# dv_mcu_mem.net
KiCad netlist of a schematic drawn in Altium Designer
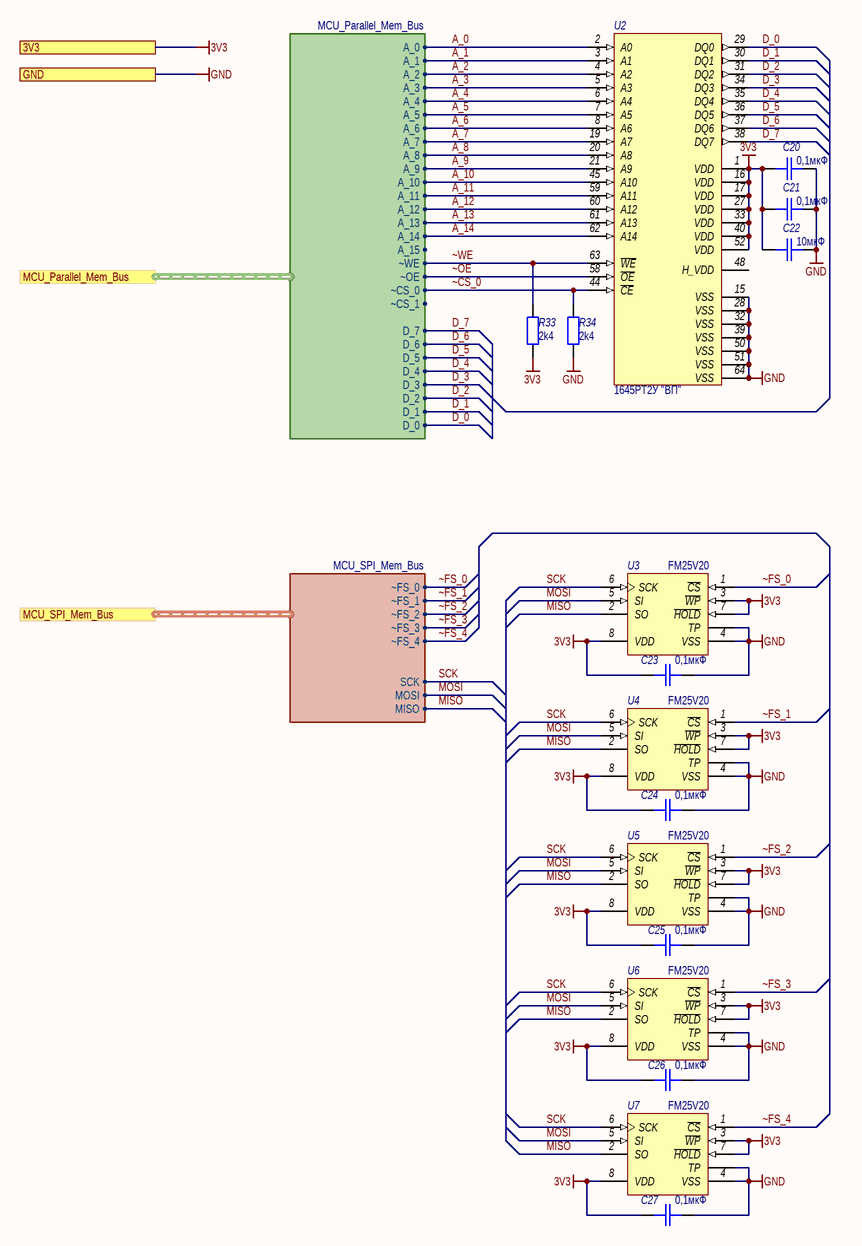
[diagram p0: dv_mcu_mem.SchDoc]

(export (version "E")
  (design (tool "Eeschema 10.0.6"))
  (components
    (comp (ref "C20")
      (value "0,1мкФ")
      (footprint "SMD_C0805")
      (description "Capacitor")
      (fields (field (name "Comment") "K10-79"))
      (libsource (lib "Passive") (part "Capacitor"))
    )
    (comp (ref "C21")
      (value "0,1мкФ")
      (footprint "SMD_C0805")
      (description "Capacitor")
      (fields (field (name "Comment") "K10-79"))
      (libsource (lib "Passive") (part "Capacitor"))
    )
    (comp (ref "C22")
      (value "10мкФ")
      (footprint "SMD_C0805")
      (description "Capacitor")
      (fields (field (name "Comment") "K10-79"))
      (libsource (lib "Passive") (part "Capacitor"))
    )
    (comp (ref "C23")
      (value "0,1мкФ")
      (footprint "SMD_C0805")
      (description "Capacitor")
      (fields (field (name "Comment") "K10-79"))
      (libsource (lib "Passive") (part "Capacitor"))
    )
    (comp (ref "C24")
      (value "0,1мкФ")
      (footprint "SMD_C0805")
      (description "Capacitor")
      (fields (field (name "Comment") "K10-79"))
      (libsource (lib "Passive") (part "Capacitor"))
    )
    (comp (ref "C25")
      (value "0,1мкФ")
      (footprint "SMD_C0805")
      (description "Capacitor")
      (fields (field (name "Comment") "K10-79"))
      (libsource (lib "Passive") (part "Capacitor"))
    )
    (comp (ref "C26")
      (value "0,1мкФ")
      (footprint "SMD_C0805")
      (description "Capacitor")
      (fields (field (name "Comment") "K10-79"))
      (libsource (lib "Passive") (part "Capacitor"))
    )
    (comp (ref "C27")
      (value "0,1мкФ")
      (footprint "SMD_C0805")
      (description "Capacitor")
      (fields (field (name "Comment") "K10-79"))
      (libsource (lib "Passive") (part "Capacitor"))
    )
    (comp (ref "R33")
      (value "2k4")
      (footprint "SMD_0805")
      (description "Resistor")
      (fields (field (name "Comment") "OSM R1-12"))
      (libsource (lib "Passive") (part "Resistor"))
    )
    (comp (ref "R34")
      (value "2k4")
      (footprint "SMD_0805")
      (description "Resistor")
      (fields (field (name "Comment") "OSM R1-12"))
      (libsource (lib "Passive") (part "Resistor"))
    )
    (comp (ref "U2")
      (value "1645RT2U VP")
      (footprint "5134.64-6")
      (fields (field (name "НАИМЕНОВАНИЕ") "1645РТ2У \"ВП\""))
      (libsource (lib "1645RT2U") (part "1645RT2U"))
    )
    (comp (ref "U3")
      (value "FM25V20")
      (footprint "TDFN-8_6x5")
      (description "2Mb Serial 3V FRAM Memory")
      (fields (field (name "НАИМЕНОВАНИЕ") "FM25V20"))
      (libsource (lib "Memory") (part "FM25V"))
    )
    (comp (ref "U4")
      (value "FM25V20")
      (footprint "TDFN-8_6x5")
      (description "2Mb Serial 3V FRAM Memory")
      (fields (field (name "НАИМЕНОВАНИЕ") "FM25V20"))
      (libsource (lib "Memory") (part "FM25V"))
    )
    (comp (ref "U5")
      (value "FM25V20")
      (footprint "TDFN-8_6x5")
      (description "2Mb Serial 3V FRAM Memory")
      (fields (field (name "НАИМЕНОВАНИЕ") "FM25V20"))
      (libsource (lib "Memory") (part "FM25V"))
    )
    (comp (ref "U6")
      (value "FM25V20")
      (footprint "TDFN-8_6x5")
      (description "2Mb Serial 3V FRAM Memory")
      (fields (field (name "НАИМЕНОВАНИЕ") "FM25V20"))
      (libsource (lib "Memory") (part "FM25V"))
    )
    (comp (ref "U7")
      (value "FM25V20")
      (footprint "TDFN-8_6x5")
      (description "2Mb Serial 3V FRAM Memory")
      (fields (field (name "НАИМЕНОВАНИЕ") "FM25V20"))
      (libsource (lib "Memory") (part "FM25V"))
    )
  )
  (nets
    (net (code "3") (name "/A_0") (class "Default")
      (node (ref "U2") (pin "2") (pinfunction "A0_2") (pintype "input"))
    )
    (net (code "4") (name "/A_1") (class "Default")
      (node (ref "U2") (pin "3") (pinfunction "A1_3") (pintype "input"))
    )
    (net (code "5") (name "/A_2") (class "Default")
      (node (ref "U2") (pin "4") (pinfunction "A2_4") (pintype "input"))
    )
    (net (code "6") (name "/A_3") (class "Default")
      (node (ref "U2") (pin "5") (pinfunction "A3_5") (pintype "input"))
    )
    (net (code "7") (name "/A_4") (class "Default")
      (node (ref "U2") (pin "6") (pinfunction "A4_6") (pintype "input"))
    )
    (net (code "8") (name "/A_5") (class "Default")
      (node (ref "U2") (pin "7") (pinfunction "A5_7") (pintype "input"))
    )
    (net (code "9") (name "/A_6") (class "Default")
      (node (ref "U2") (pin "8") (pinfunction "A6_8") (pintype "input"))
    )
    (net (code "10") (name "/A_7") (class "Default")
      (node (ref "U2") (pin "19") (pinfunction "A7_19") (pintype "input"))
    )
    (net (code "11") (name "/A_8") (class "Default")
      (node (ref "U2") (pin "20") (pinfunction "A8_20") (pintype "input"))
    )
    (net (code "12") (name "/A_9") (class "Default")
      (node (ref "U2") (pin "21") (pinfunction "A9_21") (pintype "input"))
    )
    (net (code "13") (name "/A_10") (class "Default")
      (node (ref "U2") (pin "45") (pinfunction "A10_45") (pintype "input"))
    )
    (net (code "14") (name "/A_11") (class "Default")
      (node (ref "U2") (pin "59") (pinfunction "A11_59") (pintype "input"))
    )
    (net (code "15") (name "/A_12") (class "Default")
      (node (ref "U2") (pin "60") (pinfunction "A12_60") (pintype "input"))
    )
    (net (code "16") (name "/A_13") (class "Default")
      (node (ref "U2") (pin "61") (pinfunction "A13_61") (pintype "input"))
    )
    (net (code "17") (name "/A_14") (class "Default")
      (node (ref "U2") (pin "62") (pinfunction "A14_62") (pintype "input"))
    )
    (net (code "18") (name "/D_0") (class "Default")
      (node (ref "U2") (pin "29") (pinfunction "DQ0_29") (pintype "output"))
    )
    (net (code "19") (name "/D_1") (class "Default")
      (node (ref "U2") (pin "30") (pinfunction "DQ1_30") (pintype "output"))
    )
    (net (code "20") (name "/D_2") (class "Default")
      (node (ref "U2") (pin "31") (pinfunction "DQ2_31") (pintype "output"))
    )
    (net (code "21") (name "/D_3") (class "Default")
      (node (ref "U2") (pin "34") (pinfunction "DQ3_34") (pintype "output"))
    )
    (net (code "22") (name "/D_4") (class "Default")
      (node (ref "U2") (pin "35") (pinfunction "DQ4_35") (pintype "output"))
    )
    (net (code "23") (name "/D_5") (class "Default")
      (node (ref "U2") (pin "36") (pinfunction "DQ5_36") (pintype "output"))
    )
    (net (code "24") (name "/D_6") (class "Default")
      (node (ref "U2") (pin "37") (pinfunction "DQ6_37") (pintype "output"))
    )
    (net (code "25") (name "/D_7") (class "Default")
      (node (ref "U2") (pin "38") (pinfunction "DQ7_38") (pintype "output"))
    )
    (net (code "26") (name "/MISO") (class "Default")
      (node (ref "U3") (pin "2") (pinfunction "SO_2") (pintype "tri_state"))
      (node (ref "U4") (pin "2") (pinfunction "SO_2") (pintype "tri_state"))
      (node (ref "U5") (pin "2") (pinfunction "SO_2") (pintype "tri_state"))
      (node (ref "U6") (pin "2") (pinfunction "SO_2") (pintype "tri_state"))
      (node (ref "U7") (pin "2") (pinfunction "SO_2") (pintype "tri_state"))
    )
    (net (code "27") (name "/MOSI") (class "Default")
      (node (ref "U3") (pin "5") (pinfunction "SI_5") (pintype "input"))
      (node (ref "U4") (pin "5") (pinfunction "SI_5") (pintype "input"))
      (node (ref "U5") (pin "5") (pinfunction "SI_5") (pintype "input"))
      (node (ref "U6") (pin "5") (pinfunction "SI_5") (pintype "input"))
      (node (ref "U7") (pin "5") (pinfunction "SI_5") (pintype "input"))
    )
    (net (code "28") (name "/SCK") (class "Default")
      (node (ref "U3") (pin "6") (pinfunction "SCK_6") (pintype "input"))
      (node (ref "U4") (pin "6") (pinfunction "SCK_6") (pintype "input"))
      (node (ref "U5") (pin "6") (pinfunction "SCK_6") (pintype "input"))
      (node (ref "U6") (pin "6") (pinfunction "SCK_6") (pintype "input"))
      (node (ref "U7") (pin "6") (pinfunction "SCK_6") (pintype "input"))
    )
    (net (code "31") (name "/~CS_0") (class "Default")
      (node (ref "R34") (pin "2") (pinfunction "2_2") (pintype "passive"))
      (node (ref "U2") (pin "44") (pinfunction "~{CE}_44") (pintype "input"))
    )
    (net (code "32") (name "/~FS_0") (class "Default")
      (node (ref "U3") (pin "1") (pinfunction "~{CS}_1") (pintype "input"))
    )
    (net (code "33") (name "/~FS_1") (class "Default")
      (node (ref "U4") (pin "1") (pinfunction "~{CS}_1") (pintype "input"))
    )
    (net (code "34") (name "/~FS_2") (class "Default")
      (node (ref "U5") (pin "1") (pinfunction "~{CS}_1") (pintype "input"))
    )
    (net (code "35") (name "/~FS_3") (class "Default")
      (node (ref "U6") (pin "1") (pinfunction "~{CS}_1") (pintype "input"))
    )
    (net (code "36") (name "/~FS_4") (class "Default")
      (node (ref "U7") (pin "1") (pinfunction "~{CS}_1") (pintype "input"))
    )
    (net (code "37") (name "/~OE") (class "Default")
      (node (ref "U2") (pin "58") (pinfunction "~{OE}_58") (pintype "input"))
    )
    (net (code "38") (name "/~WE") (class "Default")
      (node (ref "R33") (pin "2") (pinfunction "2_2") (pintype "passive"))
      (node (ref "U2") (pin "63") (pinfunction "~{WE}_63") (pintype "input"))
    )
    (net (code "39") (name "3V3") (class "Default")
      (node (ref "C20") (pin "1") (pinfunction "1_1") (pintype "passive"))
      (node (ref "C21") (pin "1") (pinfunction "1_1") (pintype "passive"))
      (node (ref "C22") (pin "2") (pinfunction "2_2") (pintype "passive"))
      (node (ref "C23") (pin "2") (pinfunction "2_2") (pintype "passive"))
      (node (ref "C24") (pin "2") (pinfunction "2_2") (pintype "passive"))
      (node (ref "C25") (pin "2") (pinfunction "2_2") (pintype "passive"))
      (node (ref "C26") (pin "2") (pinfunction "2_2") (pintype "passive"))
      (node (ref "C27") (pin "2") (pinfunction "2_2") (pintype "passive"))
      (node (ref "R33") (pin "1") (pinfunction "1_1") (pintype "passive"))
      (node (ref "U2") (pin "1") (pinfunction "VDD_1") (pintype "power_in"))
      (node (ref "U2") (pin "16") (pinfunction "VDD_16") (pintype "power_in"))
      (node (ref "U2") (pin "17") (pinfunction "VDD_17") (pintype "power_in"))
      (node (ref "U2") (pin "27") (pinfunction "VDD_27") (pintype "power_in"))
      (node (ref "U2") (pin "33") (pinfunction "VDD_33") (pintype "power_in"))
      (node (ref "U2") (pin "40") (pinfunction "VDD_40") (pintype "power_in"))
      (node (ref "U2") (pin "52") (pinfunction "VDD_52") (pintype "power_in"))
      (node (ref "U3") (pin "3") (pinfunction "~{WP}_3") (pintype "input"))
      (node (ref "U3") (pin "7") (pinfunction "~{HOLD}_7") (pintype "input"))
      (node (ref "U3") (pin "8") (pinfunction "VDD_8") (pintype "power_in"))
      (node (ref "U4") (pin "3") (pinfunction "~{WP}_3") (pintype "input"))
      (node (ref "U4") (pin "7") (pinfunction "~{HOLD}_7") (pintype "input"))
      (node (ref "U4") (pin "8") (pinfunction "VDD_8") (pintype "power_in"))
      (node (ref "U5") (pin "3") (pinfunction "~{WP}_3") (pintype "input"))
      (node (ref "U5") (pin "7") (pinfunction "~{HOLD}_7") (pintype "input"))
      (node (ref "U5") (pin "8") (pinfunction "VDD_8") (pintype "power_in"))
      (node (ref "U6") (pin "3") (pinfunction "~{WP}_3") (pintype "input"))
      (node (ref "U6") (pin "7") (pinfunction "~{HOLD}_7") (pintype "input"))
      (node (ref "U6") (pin "8") (pinfunction "VDD_8") (pintype "power_in"))
      (node (ref "U7") (pin "3") (pinfunction "~{WP}_3") (pintype "input"))
      (node (ref "U7") (pin "7") (pinfunction "~{HOLD}_7") (pintype "input"))
      (node (ref "U7") (pin "8") (pinfunction "VDD_8") (pintype "power_in"))
    )
    (net (code "40") (name "GND") (class "Default")
      (node (ref "C20") (pin "2") (pinfunction "2_2") (pintype "passive"))
      (node (ref "C21") (pin "2") (pinfunction "2_2") (pintype "passive"))
      (node (ref "C22") (pin "1") (pinfunction "1_1") (pintype "passive"))
      (node (ref "C23") (pin "1") (pinfunction "1_1") (pintype "passive"))
      (node (ref "C24") (pin "1") (pinfunction "1_1") (pintype "passive"))
      (node (ref "C25") (pin "1") (pinfunction "1_1") (pintype "passive"))
      (node (ref "C26") (pin "1") (pinfunction "1_1") (pintype "passive"))
      (node (ref "C27") (pin "1") (pinfunction "1_1") (pintype "passive"))
      (node (ref "R34") (pin "1") (pinfunction "1_1") (pintype "passive"))
      (node (ref "U2") (pin "15") (pinfunction "VSS_15") (pintype "power_in"))
      (node (ref "U2") (pin "28") (pinfunction "VSS_28") (pintype "power_in"))
      (node (ref "U2") (pin "32") (pinfunction "VSS_32") (pintype "power_in"))
      (node (ref "U2") (pin "39") (pinfunction "VSS_39") (pintype "power_in"))
      (node (ref "U2") (pin "50") (pinfunction "VSS_50") (pintype "power_in"))
      (node (ref "U2") (pin "51") (pinfunction "VSS_51") (pintype "power_in"))
      (node (ref "U2") (pin "64") (pinfunction "VSS_64") (pintype "power_in"))
      (node (ref "U3") (pin "4") (pinfunction "VSS_4") (pintype "power_in"))
      (node (ref "U3") (pin "TP") (pinfunction "TP_TP") (pintype "power_in"))
      (node (ref "U4") (pin "4") (pinfunction "VSS_4") (pintype "power_in"))
      (node (ref "U4") (pin "TP") (pinfunction "TP_TP") (pintype "power_in"))
      (node (ref "U5") (pin "4") (pinfunction "VSS_4") (pintype "power_in"))
      (node (ref "U5") (pin "TP") (pinfunction "TP_TP") (pintype "power_in"))
      (node (ref "U6") (pin "4") (pinfunction "VSS_4") (pintype "power_in"))
      (node (ref "U6") (pin "TP") (pinfunction "TP_TP") (pintype "power_in"))
      (node (ref "U7") (pin "4") (pinfunction "VSS_4") (pintype "power_in"))
      (node (ref "U7") (pin "TP") (pinfunction "TP_TP") (pintype "power_in"))
    )
    (net (code "41") (name "unconnected-(U2-H_VDD-Pad48)") (class "Default")
      (node (ref "U2") (pin "48") (pinfunction "H_VDD_48") (pintype "power_in"))
    )
  )
)
